# Schroom_napajanje2.net
KiCad netlist of a schematic drawn in Altium Designer
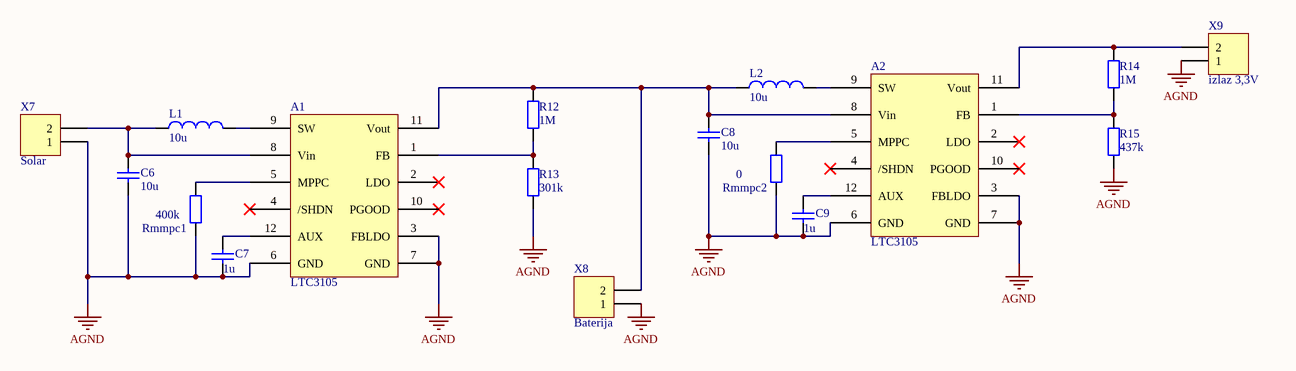
[diagram p0: Schroom_napajanje2.SchDoc]

(export (version "E")
  (design (tool "Eeschema 10.0.6"))
  (components
    (comp (ref "A1")
      (value "LTC3105")
      (footprint "SOP65P490X110-12N")
      (libsource (lib "altium-import") (part "root_0_LTC3105_"))
    )
    (comp (ref "A2")
      (value "LTC3105")
      (footprint "SOP65P490X110-12N")
      (libsource (lib "altium-import") (part "root_0_LTC3105_"))
    )
    (comp (ref "C6")
      (value "10u")
      (footprint "6-0805_N")
      (description "Capacitor")
      (fields (field (name "PUBLISHER") "Altium Limited"))
      (libsource (lib "Miscellaneous Devices") (part "Cap"))
    )
    (comp (ref "C7")
      (value "1u")
      (footprint "6-0805_N")
      (description "Capacitor")
      (fields (field (name "PUBLISHER") "Altium Limited"))
      (libsource (lib "Miscellaneous Devices") (part "Cap"))
    )
    (comp (ref "C8")
      (value "10u")
      (footprint "6-0805_N")
      (description "Capacitor")
      (fields (field (name "PUBLISHER") "Altium Limited"))
      (libsource (lib "Miscellaneous Devices") (part "Cap"))
    )
    (comp (ref "C9")
      (value "1u")
      (footprint "6-0805_N")
      (description "Capacitor")
      (fields (field (name "PUBLISHER") "Altium Limited"))
      (libsource (lib "Miscellaneous Devices") (part "Cap"))
    )
    (comp (ref "L1")
      (value "10u")
      (footprint "6-0805_N")
      (description "Inductor")
      (fields (field (name "PUBLISHER") "Altium Limited"))
      (libsource (lib "Miscellaneous Devices") (part "Inductor"))
    )
    (comp (ref "L2")
      (value "10u")
      (footprint "6-0805_N")
      (description "Inductor")
      (fields (field (name "PUBLISHER") "Altium Limited"))
      (libsource (lib "Miscellaneous Devices") (part "Inductor"))
    )
    (comp (ref "R12")
      (value "1M")
      (footprint "6-0805_N")
      (description "Resistor")
      (fields (field (name "PUBLISHER") "Altium Limited"))
      (libsource (lib "Miscellaneous Devices") (part "Res2"))
    )
    (comp (ref "R13")
      (value "301k")
      (footprint "6-0805_N")
      (description "Resistor")
      (fields (field (name "PUBLISHER") "Altium Limited"))
      (libsource (lib "") (part "Res2_1"))
    )
    (comp (ref "R14")
      (value "1M")
      (footprint "6-0805_N")
      (description "Resistor")
      (fields (field (name "PUBLISHER") "Altium Limited"))
      (libsource (lib "Miscellaneous Devices") (part "Res2"))
    )
    (comp (ref "R15")
      (value "437k")
      (footprint "6-0805_N")
      (description "Resistor")
      (fields (field (name "PUBLISHER") "Altium Limited"))
      (libsource (lib "") (part "Res2_1"))
    )
    (comp (ref "Rmmpc1")
      (value "400k")
      (footprint "6-0805_N")
      (description "Resistor")
      (fields (field (name "PUBLISHER") "Altium Limited"))
      (libsource (lib "Miscellaneous Devices") (part "Res2"))
    )
    (comp (ref "Rmmpc2")
      (value "0")
      (footprint "6-0805_N")
      (description "Resistor")
      (fields (field (name "PUBLISHER") "Altium Limited"))
      (libsource (lib "Miscellaneous Devices") (part "Res2"))
    )
    (comp (ref "X7")
      (value "Solar")
      (footprint "HDR1X2")
      (description "Header, 2-Pin")
      (fields (field (name "PUBLISHER") "Altium Limited"))
      (libsource (lib "Miscellaneous Connectors") (part "Header 2"))
    )
    (comp (ref "X8")
      (value "Baterija")
      (footprint "HDR1X2")
      (description "Header, 2-Pin")
      (fields (field (name "PUBLISHER") "Altium Limited"))
      (libsource (lib "Miscellaneous Connectors") (part "Header 2"))
    )
    (comp (ref "X9")
      (value "izlaz 3,3V")
      (footprint "HDR1X2")
      (description "Header, 2-Pin")
      (fields (field (name "PUBLISHER") "Altium Limited"))
      (libsource (lib "") (part "Header 2_1"))
    )
  )
  (nets
    (net (code "1") (name "AGND") (class "Default")
      (node (ref "A1") (pin "3") (pinfunction "FBLDO_3") (pintype "passive"))
      (node (ref "A1") (pin "6") (pinfunction "GND_6") (pintype "passive"))
      (node (ref "A1") (pin "7") (pinfunction "GND_7") (pintype "passive"))
      (node (ref "A2") (pin "3") (pinfunction "FBLDO_3") (pintype "passive"))
      (node (ref "A2") (pin "6") (pinfunction "GND_6") (pintype "passive"))
      (node (ref "A2") (pin "7") (pinfunction "GND_7") (pintype "passive"))
      (node (ref "C6") (pin "1") (pinfunction "1_1") (pintype "passive"))
      (node (ref "C7") (pin "1") (pinfunction "1_1") (pintype "passive"))
      (node (ref "C8") (pin "1") (pinfunction "1_1") (pintype "passive"))
      (node (ref "C9") (pin "1") (pinfunction "1_1") (pintype "passive"))
      (node (ref "R13") (pin "2") (pinfunction "2_2") (pintype "passive"))
      (node (ref "R15") (pin "2") (pinfunction "2_2") (pintype "passive"))
      (node (ref "Rmmpc1") (pin "1") (pinfunction "1_1") (pintype "passive"))
      (node (ref "Rmmpc2") (pin "1") (pinfunction "1_1") (pintype "passive"))
      (node (ref "X7") (pin "1") (pinfunction "1_1") (pintype "passive"))
      (node (ref "X8") (pin "1") (pinfunction "1_1") (pintype "passive"))
      (node (ref "X9") (pin "1") (pinfunction "1_1") (pintype "passive"))
    )
    (net (code "2") (name "Net-(A1-AUX)") (class "Default")
      (node (ref "A1") (pin "12") (pinfunction "AUX_12") (pintype "passive"))
      (node (ref "C7") (pin "2") (pinfunction "2_2") (pintype "passive"))
    )
    (net (code "3") (name "Net-(A1-FB)") (class "Default")
      (node (ref "A1") (pin "1") (pinfunction "FB_1") (pintype "passive"))
      (node (ref "R12") (pin "1") (pinfunction "1_1") (pintype "passive"))
      (node (ref "R13") (pin "1") (pinfunction "1_1") (pintype "passive"))
    )
    (net (code "4") (name "Net-(A1-MPPC)") (class "Default")
      (node (ref "A1") (pin "5") (pinfunction "MPPC_5") (pintype "passive"))
      (node (ref "Rmmpc1") (pin "2") (pinfunction "2_2") (pintype "passive"))
    )
    (net (code "5") (name "Net-(A1-SW)") (class "Default")
      (node (ref "A1") (pin "9") (pinfunction "SW_9") (pintype "passive"))
      (node (ref "L1") (pin "2") (pinfunction "2_2") (pintype "passive"))
    )
    (net (code "6") (name "Net-(A1-Vin)") (class "Default")
      (node (ref "A1") (pin "8") (pinfunction "Vin_8") (pintype "passive"))
      (node (ref "C6") (pin "2") (pinfunction "2_2") (pintype "passive"))
      (node (ref "L1") (pin "1") (pinfunction "1_1") (pintype "passive"))
      (node (ref "X7") (pin "2") (pinfunction "2_2") (pintype "passive"))
    )
    (net (code "7") (name "Net-(A1-Vout)") (class "Default")
      (node (ref "A1") (pin "11") (pinfunction "Vout_11") (pintype "passive"))
      (node (ref "A2") (pin "8") (pinfunction "Vin_8") (pintype "passive"))
      (node (ref "C8") (pin "2") (pinfunction "2_2") (pintype "passive"))
      (node (ref "L2") (pin "1") (pinfunction "1_1") (pintype "passive"))
      (node (ref "R12") (pin "2") (pinfunction "2_2") (pintype "passive"))
      (node (ref "X8") (pin "2") (pinfunction "2_2") (pintype "passive"))
    )
    (net (code "8") (name "Net-(A2-AUX)") (class "Default")
      (node (ref "A2") (pin "12") (pinfunction "AUX_12") (pintype "passive"))
      (node (ref "C9") (pin "2") (pinfunction "2_2") (pintype "passive"))
    )
    (net (code "9") (name "Net-(A2-FB)") (class "Default")
      (node (ref "A2") (pin "1") (pinfunction "FB_1") (pintype "passive"))
      (node (ref "R14") (pin "1") (pinfunction "1_1") (pintype "passive"))
      (node (ref "R15") (pin "1") (pinfunction "1_1") (pintype "passive"))
    )
    (net (code "10") (name "Net-(A2-MPPC)") (class "Default")
      (node (ref "A2") (pin "5") (pinfunction "MPPC_5") (pintype "passive"))
      (node (ref "Rmmpc2") (pin "2") (pinfunction "2_2") (pintype "passive"))
    )
    (net (code "11") (name "Net-(A2-SW)") (class "Default")
      (node (ref "A2") (pin "9") (pinfunction "SW_9") (pintype "passive"))
      (node (ref "L2") (pin "2") (pinfunction "2_2") (pintype "passive"))
    )
    (net (code "12") (name "Net-(A2-Vout)") (class "Default")
      (node (ref "A2") (pin "11") (pinfunction "Vout_11") (pintype "passive"))
      (node (ref "R14") (pin "2") (pinfunction "2_2") (pintype "passive"))
      (node (ref "X9") (pin "2") (pinfunction "2_2") (pintype "passive"))
    )
    (net (code "13") (name "unconnected-(A1-LDO-Pad2)") (class "Default")
      (node (ref "A1") (pin "2") (pinfunction "LDO_2") (pintype "passive+no_connect"))
    )
    (net (code "14") (name "unconnected-(A1-PGOOD-Pad10)") (class "Default")
      (node (ref "A1") (pin "10") (pinfunction "PGOOD_10") (pintype "passive+no_connect"))
    )
    (net (code "15") (name "unconnected-(A1-{slash}SHDN-Pad4)") (class "Default")
      (node (ref "A1") (pin "4") (pinfunction "/SHDN_4") (pintype "passive+no_connect"))
    )
    (net (code "16") (name "unconnected-(A2-LDO-Pad2)") (class "Default")
      (node (ref "A2") (pin "2") (pinfunction "LDO_2") (pintype "passive+no_connect"))
    )
    (net (code "17") (name "unconnected-(A2-PGOOD-Pad10)") (class "Default")
      (node (ref "A2") (pin "10") (pinfunction "PGOOD_10") (pintype "passive+no_connect"))
    )
    (net (code "18") (name "unconnected-(A2-{slash}SHDN-Pad4)") (class "Default")
      (node (ref "A2") (pin "4") (pinfunction "/SHDN_4") (pintype "passive+no_connect"))
    )
  )
)
